# New_Project_2026-01-03_13-52-35.net
KiCad netlist of a schematic drawn in EasyEDA Pro
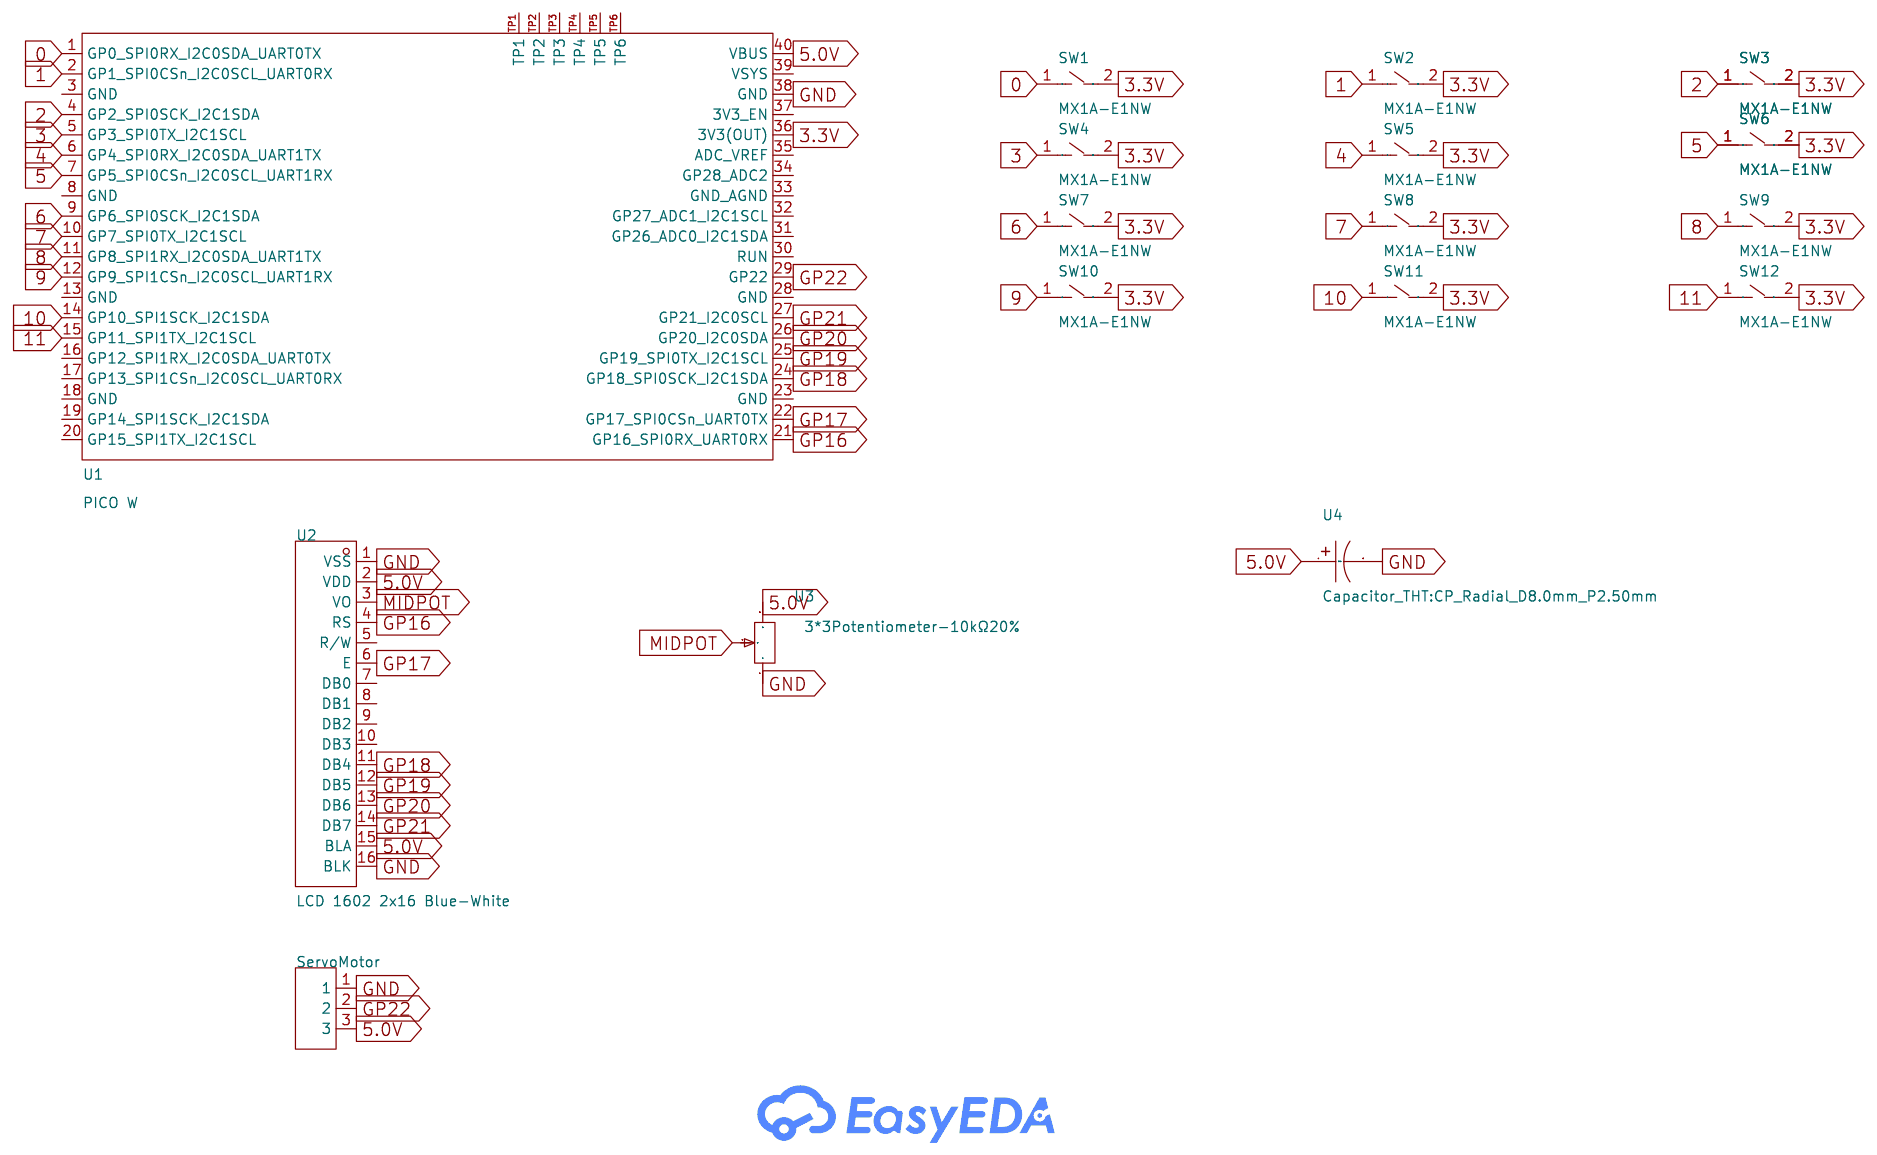
[diagram p0: schematic sheet]

(export (version "E")
  (design (tool "Eeschema 10.0.6"))
  (components
    (comp (ref "ServoMotor")
      (value "~")
      (footprint "easyedapro:HDR-TH_3P-P2.54-V-M")
      (libsource (lib "easyedapro") (part "PZ254V-11-03P_C2937625"))
    )
    (comp (ref "SW1")
      (value "MX1A-E1NW")
      (footprint "easyedapro:SW-TH_MX1A-E1NW")
      (fields (field (name "Manufacturer") "CHERRY"))
      (libsource (lib "easyedapro") (part "MX1A-E1NW"))
    )
    (comp (ref "SW2")
      (value "MX1A-E1NW")
      (footprint "easyedapro:SW-TH_MX1A-E1NW")
      (fields (field (name "Manufacturer") "CHERRY"))
      (libsource (lib "easyedapro") (part "MX1A-E1NW"))
    )
    (comp (ref "SW3")
      (value "MX1A-E1NW")
      (footprint "easyedapro:SW-TH_MX1A-E1NW")
      (fields (field (name "Manufacturer") "CHERRY"))
      (libsource (lib "easyedapro") (part "MX1A-E1NW"))
    )
    (comp (ref "SW4")
      (value "MX1A-E1NW")
      (footprint "easyedapro:SW-TH_MX1A-E1NW")
      (fields (field (name "Manufacturer") "CHERRY"))
      (libsource (lib "easyedapro") (part "MX1A-E1NW"))
    )
    (comp (ref "SW5")
      (value "MX1A-E1NW")
      (footprint "easyedapro:SW-TH_MX1A-E1NW")
      (fields (field (name "Manufacturer") "CHERRY"))
      (libsource (lib "easyedapro") (part "MX1A-E1NW"))
    )
    (comp (ref "SW6")
      (value "MX1A-E1NW")
      (footprint "easyedapro:SW-TH_MX1A-E1NW")
      (fields (field (name "Manufacturer") "CHERRY"))
      (libsource (lib "easyedapro") (part "MX1A-E1NW"))
    )
    (comp (ref "SW7")
      (value "MX1A-E1NW")
      (footprint "easyedapro:SW-TH_MX1A-E1NW")
      (fields (field (name "Manufacturer") "CHERRY"))
      (libsource (lib "easyedapro") (part "MX1A-E1NW"))
    )
    (comp (ref "SW8")
      (value "MX1A-E1NW")
      (footprint "easyedapro:SW-TH_MX1A-E1NW")
      (fields (field (name "Manufacturer") "CHERRY"))
      (libsource (lib "easyedapro") (part "MX1A-E1NW"))
    )
    (comp (ref "SW9")
      (value "MX1A-E1NW")
      (footprint "easyedapro:SW-TH_MX1A-E1NW")
      (fields (field (name "Manufacturer") "CHERRY"))
      (libsource (lib "easyedapro") (part "MX1A-E1NW"))
    )
    (comp (ref "SW10")
      (value "MX1A-E1NW")
      (footprint "easyedapro:SW-TH_MX1A-E1NW")
      (fields (field (name "Manufacturer") "CHERRY"))
      (libsource (lib "easyedapro") (part "MX1A-E1NW"))
    )
    (comp (ref "SW11")
      (value "MX1A-E1NW")
      (footprint "easyedapro:SW-TH_MX1A-E1NW")
      (fields (field (name "Manufacturer") "CHERRY"))
      (libsource (lib "easyedapro") (part "MX1A-E1NW"))
    )
    (comp (ref "SW12")
      (value "MX1A-E1NW")
      (footprint "easyedapro:SW-TH_MX1A-E1NW")
      (fields (field (name "Manufacturer") "CHERRY"))
      (libsource (lib "easyedapro") (part "MX1A-E1NW"))
    )
    (comp (ref "U1")
      (value "PICO W")
      (footprint "easyedapro:COMM-SMD_L51.0-W21.0-P2.54_PICOW")
      (fields (field (name "Manufacturer") "Raspberry Pi(树莓派)"))
      (libsource (lib "easyedapro") (part "PICO W"))
    )
    (comp (ref "U2")
      (value "LCD 1602 2x16 Blue-White")
      (footprint "easyedapro:LCD-TH_LCD-1602-2X16-BLUE-WHITE")
      (description "Main Control Chip:HD44780 Interface Type:-")
      (fields (field (name "Manufacturer") "Universal Microelectronics"))
      (libsource (lib "easyedapro") (part "LCD 1602 2X16 BLUE-WHITE_C17667002"))
    )
    (comp (ref "U3")
      (value "3*3Potentiometer-10kΩ20%")
      (footprint "easyedapro:RES-ADJ-SMD_VG039NCH")
      (libsource (lib "easyedapro") (part "3*3POTENTIOMETER-10KΩ20%"))
    )
    (comp (ref "U4")
      (value "Capacitor_THT:CP_Radial_D8.0mm_P2.50mm")
      (footprint "easyedapro:CAP-TH_BD8.0-P3.50-D0.6-FD")
      (libsource (lib "easyedapro") (part "CAPACITOR_THT{colon}CP_RADIAL_D8.0MM_P2.50MM"))
    )
  )
  (nets
    (net (code "1") (name "0") (class "Default")
      (node (ref "SW1") (pin "1") (pinfunction "1_1") (pintype "unspecified"))
      (node (ref "U1") (pin "1") (pinfunction "GP0_SPI0RX_I2C0SDA_UART0TX_1") (pintype "unspecified"))
    )
    (net (code "2") (name "1") (class "Default")
      (node (ref "SW2") (pin "1") (pinfunction "1_1") (pintype "unspecified"))
      (node (ref "U1") (pin "2") (pinfunction "GP1_SPI0CSn_I2C0SCL_UART0RX_2") (pintype "unspecified"))
    )
    (net (code "3") (name "2") (class "Default")
      (node (ref "SW3") (pin "1") (pinfunction "1_1") (pintype "unspecified"))
      (node (ref "U1") (pin "4") (pinfunction "GP2_SPI0SCK_I2C1SDA_4") (pintype "unspecified"))
    )
    (net (code "4") (name "3") (class "Default")
      (node (ref "SW4") (pin "1") (pinfunction "1_1") (pintype "unspecified"))
      (node (ref "U1") (pin "5") (pinfunction "GP3_SPI0TX_I2C1SCL_5") (pintype "unspecified"))
    )
    (net (code "5") (name "3.3V") (class "Default")
      (node (ref "SW1") (pin "2") (pinfunction "2_2") (pintype "unspecified"))
      (node (ref "SW10") (pin "2") (pinfunction "2_2") (pintype "unspecified"))
      (node (ref "SW11") (pin "2") (pinfunction "2_2") (pintype "unspecified"))
      (node (ref "SW12") (pin "2") (pinfunction "2_2") (pintype "unspecified"))
      (node (ref "SW2") (pin "2") (pinfunction "2_2") (pintype "unspecified"))
      (node (ref "SW3") (pin "2") (pinfunction "2_2") (pintype "unspecified"))
      (node (ref "SW4") (pin "2") (pinfunction "2_2") (pintype "unspecified"))
      (node (ref "SW5") (pin "2") (pinfunction "2_2") (pintype "unspecified"))
      (node (ref "SW6") (pin "2") (pinfunction "2_2") (pintype "unspecified"))
      (node (ref "SW7") (pin "2") (pinfunction "2_2") (pintype "unspecified"))
      (node (ref "SW8") (pin "2") (pinfunction "2_2") (pintype "unspecified"))
      (node (ref "SW9") (pin "2") (pinfunction "2_2") (pintype "unspecified"))
      (node (ref "U1") (pin "36") (pinfunction "3V3(OUT)_36") (pintype "unspecified"))
    )
    (net (code "6") (name "4") (class "Default")
      (node (ref "SW5") (pin "1") (pinfunction "1_1") (pintype "unspecified"))
      (node (ref "U1") (pin "6") (pinfunction "GP4_SPI0RX_I2C0SDA_UART1TX_6") (pintype "unspecified"))
    )
    (net (code "7") (name "5") (class "Default")
      (node (ref "SW6") (pin "1") (pinfunction "1_1") (pintype "unspecified"))
      (node (ref "U1") (pin "7") (pinfunction "GP5_SPI0CSn_I2C0SCL_UART1RX_7") (pintype "unspecified"))
    )
    (net (code "8") (name "5.0V") (class "Default")
      (node (ref "ServoMotor") (pin "3") (pinfunction "3_3") (pintype "unspecified"))
      (node (ref "U1") (pin "40") (pinfunction "VBUS_40") (pintype "unspecified"))
      (node (ref "U2") (pin "15") (pinfunction "BLA_15") (pintype "unspecified"))
      (node (ref "U2") (pin "2") (pinfunction "VDD_2") (pintype "unspecified"))
      (node (ref "U3") (pin "3") (pinfunction "3_3") (pintype "input"))
      (node (ref "U4") (pin "1") (pinfunction "1_1") (pintype "unspecified"))
    )
    (net (code "9") (name "6") (class "Default")
      (node (ref "SW7") (pin "1") (pinfunction "1_1") (pintype "unspecified"))
      (node (ref "U1") (pin "9") (pinfunction "GP6_SPI0SCK_I2C1SDA_9") (pintype "unspecified"))
    )
    (net (code "10") (name "7") (class "Default")
      (node (ref "SW8") (pin "1") (pinfunction "1_1") (pintype "unspecified"))
      (node (ref "U1") (pin "10") (pinfunction "GP7_SPI0TX_I2C1SCL_10") (pintype "unspecified"))
    )
    (net (code "11") (name "8") (class "Default")
      (node (ref "SW9") (pin "1") (pinfunction "1_1") (pintype "unspecified"))
      (node (ref "U1") (pin "11") (pinfunction "GP8_SPI1RX_I2C0SDA_UART1TX_11") (pintype "unspecified"))
    )
    (net (code "12") (name "9") (class "Default")
      (node (ref "SW10") (pin "1") (pinfunction "1_1") (pintype "unspecified"))
      (node (ref "U1") (pin "12") (pinfunction "GP9_SPI1CSn_I2C0SCL_UART1RX_12") (pintype "unspecified"))
    )
    (net (code "13") (name "10") (class "Default")
      (node (ref "SW11") (pin "1") (pinfunction "1_1") (pintype "unspecified"))
      (node (ref "U1") (pin "14") (pinfunction "GP10_SPI1SCK_I2C1SDA_14") (pintype "unspecified"))
    )
    (net (code "14") (name "11") (class "Default")
      (node (ref "SW12") (pin "1") (pinfunction "1_1") (pintype "unspecified"))
      (node (ref "U1") (pin "15") (pinfunction "GP11_SPI1TX_I2C1SCL_15") (pintype "unspecified"))
    )
    (net (code "15") (name "GND") (class "Default")
      (node (ref "ServoMotor") (pin "1") (pinfunction "1_1") (pintype "unspecified"))
      (node (ref "U1") (pin "38") (pinfunction "GND_38") (pintype "unspecified"))
      (node (ref "U2") (pin "1") (pinfunction "VSS_1") (pintype "unspecified"))
      (node (ref "U2") (pin "16") (pinfunction "BLK_16") (pintype "unspecified"))
      (node (ref "U3") (pin "1") (pinfunction "1_1") (pintype "input"))
      (node (ref "U4") (pin "2") (pinfunction "2_2") (pintype "unspecified"))
    )
    (net (code "16") (name "GP16") (class "Default")
      (node (ref "U1") (pin "21") (pinfunction "GP16_SPI0RX_UART0RX_21") (pintype "unspecified"))
      (node (ref "U2") (pin "4") (pinfunction "RS_4") (pintype "unspecified"))
    )
    (net (code "17") (name "GP17") (class "Default")
      (node (ref "U1") (pin "22") (pinfunction "GP17_SPI0CSn_UART0TX_22") (pintype "unspecified"))
      (node (ref "U2") (pin "6") (pinfunction "E_6") (pintype "unspecified"))
    )
    (net (code "18") (name "GP18") (class "Default")
      (node (ref "U1") (pin "24") (pinfunction "GP18_SPI0SCK_I2C1SDA_24") (pintype "unspecified"))
      (node (ref "U2") (pin "11") (pinfunction "DB4_11") (pintype "unspecified"))
    )
    (net (code "19") (name "GP19") (class "Default")
      (node (ref "U1") (pin "25") (pinfunction "GP19_SPI0TX_I2C1SCL_25") (pintype "unspecified"))
      (node (ref "U2") (pin "12") (pinfunction "DB5_12") (pintype "unspecified"))
    )
    (net (code "20") (name "GP20") (class "Default")
      (node (ref "U1") (pin "26") (pinfunction "GP20_I2C0SDA_26") (pintype "unspecified"))
      (node (ref "U2") (pin "13") (pinfunction "DB6_13") (pintype "unspecified"))
    )
    (net (code "21") (name "GP21") (class "Default")
      (node (ref "U1") (pin "27") (pinfunction "GP21_I2C0SCL_27") (pintype "unspecified"))
      (node (ref "U2") (pin "14") (pinfunction "DB7_14") (pintype "unspecified"))
    )
    (net (code "22") (name "GP22") (class "Default")
      (node (ref "ServoMotor") (pin "2") (pinfunction "2_2") (pintype "unspecified"))
      (node (ref "U1") (pin "29") (pinfunction "GP22_29") (pintype "unspecified"))
    )
    (net (code "23") (name "MIDPOT") (class "Default")
      (node (ref "U2") (pin "3") (pinfunction "VO_3") (pintype "unspecified"))
      (node (ref "U3") (pin "2") (pinfunction "2_2") (pintype "input"))
    )
    (net (code "24") (name "unconnected-(U1-3V3_EN-Pad37)") (class "Default")
      (node (ref "U1") (pin "37") (pinfunction "3V3_EN_37") (pintype "unspecified"))
    )
    (net (code "25") (name "unconnected-(U1-ADC_VREF-Pad35)") (class "Default")
      (node (ref "U1") (pin "35") (pinfunction "ADC_VREF_35") (pintype "unspecified"))
    )
    (net (code "26") (name "unconnected-(U1-GND-Pad3)") (class "Default")
      (node (ref "U1") (pin "3") (pinfunction "GND_3") (pintype "unspecified"))
    )
    (net (code "27") (name "unconnected-(U1-GND-Pad8)") (class "Default")
      (node (ref "U1") (pin "8") (pinfunction "GND_8") (pintype "unspecified"))
    )
    (net (code "28") (name "unconnected-(U1-GND-Pad13)") (class "Default")
      (node (ref "U1") (pin "13") (pinfunction "GND_13") (pintype "unspecified"))
    )
    (net (code "29") (name "unconnected-(U1-GND-Pad18)") (class "Default")
      (node (ref "U1") (pin "18") (pinfunction "GND_18") (pintype "unspecified"))
    )
    (net (code "30") (name "unconnected-(U1-GND-Pad23)") (class "Default")
      (node (ref "U1") (pin "23") (pinfunction "GND_23") (pintype "unspecified"))
    )
    (net (code "31") (name "unconnected-(U1-GND-Pad28)") (class "Default")
      (node (ref "U1") (pin "28") (pinfunction "GND_28") (pintype "unspecified"))
    )
    (net (code "32") (name "unconnected-(U1-GND_AGND-Pad33)") (class "Default")
      (node (ref "U1") (pin "33") (pinfunction "GND_AGND_33") (pintype "unspecified"))
    )
    (net (code "33") (name "unconnected-(U1-GP12_SPI1RX_I2C0SDA_UART0TX-Pad16)") (class "Default")
      (node (ref "U1") (pin "16") (pinfunction "GP12_SPI1RX_I2C0SDA_UART0TX_16") (pintype "unspecified"))
    )
    (net (code "34") (name "unconnected-(U1-GP13_SPI1CSn_I2C0SCL_UART0RX-Pad17)") (class "Default")
      (node (ref "U1") (pin "17") (pinfunction "GP13_SPI1CSn_I2C0SCL_UART0RX_17") (pintype "unspecified"))
    )
    (net (code "35") (name "unconnected-(U1-GP14_SPI1SCK_I2C1SDA-Pad19)") (class "Default")
      (node (ref "U1") (pin "19") (pinfunction "GP14_SPI1SCK_I2C1SDA_19") (pintype "unspecified"))
    )
    (net (code "36") (name "unconnected-(U1-GP15_SPI1TX_I2C1SCL-Pad20)") (class "Default")
      (node (ref "U1") (pin "20") (pinfunction "GP15_SPI1TX_I2C1SCL_20") (pintype "unspecified"))
    )
    (net (code "37") (name "unconnected-(U1-GP26_ADC0_I2C1SDA-Pad31)") (class "Default")
      (node (ref "U1") (pin "31") (pinfunction "GP26_ADC0_I2C1SDA_31") (pintype "unspecified"))
    )
    (net (code "38") (name "unconnected-(U1-GP27_ADC1_I2C1SCL-Pad32)") (class "Default")
      (node (ref "U1") (pin "32") (pinfunction "GP27_ADC1_I2C1SCL_32") (pintype "unspecified"))
    )
    (net (code "39") (name "unconnected-(U1-GP28_ADC2-Pad34)") (class "Default")
      (node (ref "U1") (pin "34") (pinfunction "GP28_ADC2_34") (pintype "unspecified"))
    )
    (net (code "40") (name "unconnected-(U1-PadTP1)") (class "Default")
      (node (ref "U1") (pin "TP1") (pinfunction "TP1_TP1") (pintype "unspecified"))
    )
    (net (code "41") (name "unconnected-(U1-PadTP2)") (class "Default")
      (node (ref "U1") (pin "TP2") (pinfunction "TP2_TP2") (pintype "unspecified"))
    )
    (net (code "42") (name "unconnected-(U1-PadTP3)") (class "Default")
      (node (ref "U1") (pin "TP3") (pinfunction "TP3_TP3") (pintype "unspecified"))
    )
    (net (code "43") (name "unconnected-(U1-PadTP4)") (class "Default")
      (node (ref "U1") (pin "TP4") (pinfunction "TP4_TP4") (pintype "unspecified"))
    )
    (net (code "44") (name "unconnected-(U1-PadTP5)") (class "Default")
      (node (ref "U1") (pin "TP5") (pinfunction "TP5_TP5") (pintype "unspecified"))
    )
    (net (code "45") (name "unconnected-(U1-PadTP6)") (class "Default")
      (node (ref "U1") (pin "TP6") (pinfunction "TP6_TP6") (pintype "unspecified"))
    )
    (net (code "46") (name "unconnected-(U1-RUN-Pad30)") (class "Default")
      (node (ref "U1") (pin "30") (pinfunction "RUN_30") (pintype "unspecified"))
    )
    (net (code "47") (name "unconnected-(U1-VSYS-Pad39)") (class "Default")
      (node (ref "U1") (pin "39") (pinfunction "VSYS_39") (pintype "unspecified"))
    )
    (net (code "48") (name "unconnected-(U2-DB0-Pad7)") (class "Default")
      (node (ref "U2") (pin "7") (pinfunction "DB0_7") (pintype "unspecified"))
    )
    (net (code "49") (name "unconnected-(U2-DB1-Pad8)") (class "Default")
      (node (ref "U2") (pin "8") (pinfunction "DB1_8") (pintype "unspecified"))
    )
    (net (code "50") (name "unconnected-(U2-DB2-Pad9)") (class "Default")
      (node (ref "U2") (pin "9") (pinfunction "DB2_9") (pintype "unspecified"))
    )
    (net (code "51") (name "unconnected-(U2-DB3-Pad10)") (class "Default")
      (node (ref "U2") (pin "10") (pinfunction "DB3_10") (pintype "unspecified"))
    )
    (net (code "52") (name "unconnected-(U2-R{slash}W-Pad5)") (class "Default")
      (node (ref "U2") (pin "5") (pinfunction "R/W_5") (pintype "unspecified"))
    )
  )
)
